# DistBoard.net
KiCad netlist of a schematic drawn in Altium Designer
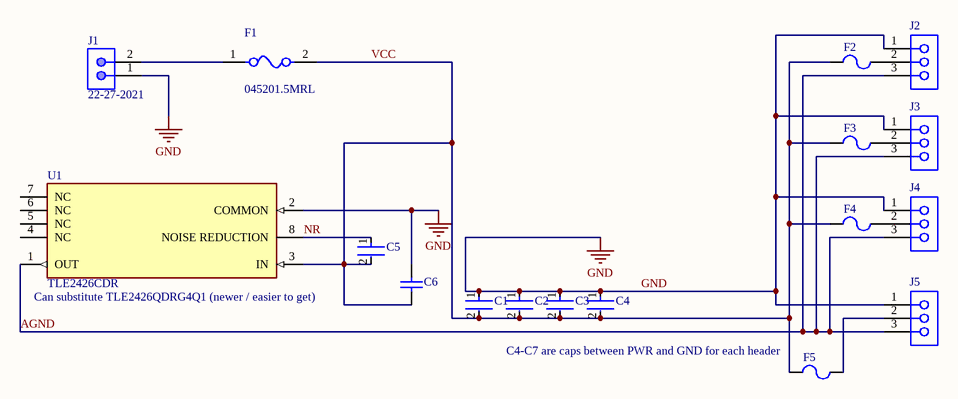
[diagram p0: DistBoard.SchDoc]

(export (version "E")
  (design (tool "Eeschema 10.0.6"))
  (components
    (comp (ref "C1")
      (value "GCJ21BR71H105KA01L")
      (footprint "FP-GCJ21B-0_3-IPC_B")
      (fields (field (name "TOLERANCE") "10%") (field (name "MANUFACTURER") "Murata"))
      (libsource (lib "Altium Content Vault") (part "02cd4be3c70576c341d710602a673aa"))
    )
    (comp (ref "C2")
      (value "GCJ21BR71H105KA01L")
      (footprint "FP-GCJ21B-0_3-IPC_B")
      (fields (field (name "TOLERANCE") "10%") (field (name "MANUFACTURER") "Murata"))
      (libsource (lib "Altium Content Vault") (part "02cd4be3c70576c341d710602a673aa"))
    )
    (comp (ref "C3")
      (value "GCJ21BR71H105KA01L")
      (footprint "FP-GCJ21B-0_3-IPC_B")
      (fields (field (name "TOLERANCE") "10%") (field (name "MANUFACTURER") "Murata"))
      (libsource (lib "Altium Content Vault") (part "02cd4be3c70576c341d710602a673aa"))
    )
    (comp (ref "C4")
      (value "GCJ21BR71H105KA01L")
      (footprint "FP-GCJ21B-0_3-IPC_B")
      (fields (field (name "TOLERANCE") "10%") (field (name "MANUFACTURER") "Murata"))
      (libsource (lib "Altium Content Vault") (part "02cd4be3c70576c341d710602a673aa"))
    )
    (comp (ref "C5")
      (value "GCD21BR71H104KA01L")
      (footprint "FP-GCD21B-0_15-IPC_C")
      (fields (field (name "TOLERANCE") "10%") (field (name "MANUFACTURER") "Murata"))
      (libsource (lib "Altium Content Vault") (part "b4654b650e69147ec39a6b967a45e02"))
    )
    (comp (ref "C6")
      (value "C1206C105K5RACTU")
      (footprint "CAPC3216X110X50LL20T25")
      (description "Chip Capacitor, 1 uF, +/- 10%, 50 V, -55 to 125 degC, 1206 (3216 Metric), RoHS, Tape and Reel")
      (fields (field (name "MANUFACTURER") "Kemet") (field (name "TOLERANCE") "10%"))
      (libsource (lib "Altium Content Vault") (part "CAP-NP-2"))
    )
    (comp (ref "F1")
      (value "045201.5MRL")
      (footprint "FP-0452-MFG")
      (description "FUSE BRD MNT 1.5A 125VAC/VDC SMD")
      (fields
        (field (name "MANUFACTURER") "Littelfuse Inc")
        (field (name "OCTOPART") "https://octopart.com/045201.5mrl-littelfuse-566412")
      )
      (libsource (lib "Altium Content Vault") (part "5bcf9b9f640e542cf0359d10258e979"))
    )
    (comp (ref "F2")
      (value "0459.250UR")
      (footprint "LFUS-459_V")
      (description "Fuse, 125 V, 250 mA, -55 to 125 degC, 2-Pin SMD, RoHS, Tape and Reel")
      (fields (field (name "MANUFACTURER") "Littelfuse"))
      (libsource (lib "Altium Content Vault") (part "FUSE-2"))
    )
    (comp (ref "F3")
      (value "0459.250UR")
      (footprint "LFUS-459_V")
      (description "Fuse, 125 V, 250 mA, -55 to 125 degC, 2-Pin SMD, RoHS, Tape and Reel")
      (fields (field (name "MANUFACTURER") "Littelfuse"))
      (libsource (lib "Altium Content Vault") (part "FUSE-2"))
    )
    (comp (ref "F4")
      (value "0459.250UR")
      (footprint "LFUS-459_V")
      (description "Fuse, 125 V, 250 mA, -55 to 125 degC, 2-Pin SMD, RoHS, Tape and Reel")
      (fields (field (name "MANUFACTURER") "Littelfuse"))
      (libsource (lib "Altium Content Vault") (part "FUSE-2"))
    )
    (comp (ref "F5")
      (value "0459.250UR")
      (footprint "LFUS-459_V")
      (description "Fuse, 125 V, 250 mA, -55 to 125 degC, 2-Pin SMD, RoHS, Tape and Reel")
      (fields (field (name "MANUFACTURER") "Littelfuse"))
      (libsource (lib "Altium Content Vault") (part "FUSE-2"))
    )
    (comp (ref "J1")
      (value "22-27-2021")
      (footprint "MOLX-22-27-2021_V")
      (fields (field (name "MANUFACTURER") "Molex") (field (name "PARTNUMBER") "0022272021"))
      (libsource (lib "Altium Content Vault") (part "CN-1P-M-R2"))
    )
    (comp (ref "J2")
      (value "SSM-103-L-SV")
      (footprint "SMTC-SSM-103-X-SV")
      (fields (field (name "MANUFACTURER") "Samtec"))
      (libsource (lib "Altium Content Vault") (part "SMTC-SSM-103-X-SV"))
    )
    (comp (ref "J3")
      (value "SSM-103-L-SV")
      (footprint "SMTC-SSM-103-X-SV")
      (fields (field (name "MANUFACTURER") "Samtec"))
      (libsource (lib "Altium Content Vault") (part "SMTC-SSM-103-X-SV"))
    )
    (comp (ref "J4")
      (value "SSM-103-L-SV")
      (footprint "SMTC-SSM-103-X-SV")
      (fields (field (name "MANUFACTURER") "Samtec"))
      (libsource (lib "Altium Content Vault") (part "SMTC-SSM-103-X-SV"))
    )
    (comp (ref "J5")
      (value "SSM-103-L-SV")
      (footprint "SMTC-SSM-103-X-SV")
      (fields (field (name "MANUFACTURER") "Samtec"))
      (libsource (lib "Altium Content Vault") (part "SMTC-SSM-103-X-SV"))
    )
    (comp (ref "U1")
      (value "TLE2426CDR")
      (footprint "FP-D0008A-IPC_B")
      (fields (field (name "TOLERANCE") "1%") (field (name "MANUFACTURER") "Texas Instruments"))
      (libsource (lib "Altium Content Vault") (part "6a05ed44ac4318f8a6b310f721958da"))
    )
  )
  (nets
    (net (code "1") (name "/AGND") (class "Default")
      (node (ref "J2") (pin "3") (pinfunction "3_3") (pintype "passive"))
      (node (ref "J3") (pin "3") (pinfunction "3_3") (pintype "passive"))
      (node (ref "J4") (pin "3") (pinfunction "3_3") (pintype "passive"))
      (node (ref "J5") (pin "3") (pinfunction "3_3") (pintype "passive"))
      (node (ref "U1") (pin "1") (pinfunction "OUT_1") (pintype "output"))
    )
    (net (code "2") (name "/NR") (class "Default")
      (node (ref "C5") (pin "1") (pinfunction "1_1") (pintype "passive"))
      (node (ref "U1") (pin "8") (pinfunction "NOISE_REDUCTION_8") (pintype "passive"))
    )
    (net (code "3") (name "/VCC") (class "Default")
      (node (ref "C1") (pin "2") (pinfunction "2_2") (pintype "passive"))
      (node (ref "C2") (pin "2") (pinfunction "2_2") (pintype "passive"))
      (node (ref "C3") (pin "2") (pinfunction "2_2") (pintype "passive"))
      (node (ref "C4") (pin "2") (pinfunction "2_2") (pintype "passive"))
      (node (ref "C5") (pin "2") (pinfunction "2_2") (pintype "passive"))
      (node (ref "C6") (pin "1") (pinfunction "1_1") (pintype "passive"))
      (node (ref "F1") (pin "2") (pinfunction "2_2") (pintype "passive"))
      (node (ref "F2") (pin "1") (pinfunction "1_1") (pintype "passive"))
      (node (ref "F3") (pin "1") (pinfunction "1_1") (pintype "passive"))
      (node (ref "F4") (pin "1") (pinfunction "1_1") (pintype "passive"))
      (node (ref "F5") (pin "1") (pinfunction "1_1") (pintype "passive"))
      (node (ref "U1") (pin "3") (pinfunction "IN_3") (pintype "input"))
    )
    (net (code "4") (name "GND") (class "Default")
      (node (ref "C1") (pin "1") (pinfunction "1_1") (pintype "passive"))
      (node (ref "C2") (pin "1") (pinfunction "1_1") (pintype "passive"))
      (node (ref "C3") (pin "1") (pinfunction "1_1") (pintype "passive"))
      (node (ref "C4") (pin "1") (pinfunction "1_1") (pintype "passive"))
      (node (ref "C6") (pin "2") (pinfunction "2_2") (pintype "passive"))
      (node (ref "J1") (pin "1") (pinfunction "1_1") (pintype "passive"))
      (node (ref "J2") (pin "1") (pinfunction "1_1") (pintype "passive"))
      (node (ref "J3") (pin "1") (pinfunction "1_1") (pintype "passive"))
      (node (ref "J4") (pin "1") (pinfunction "1_1") (pintype "passive"))
      (node (ref "J5") (pin "1") (pinfunction "1_1") (pintype "passive"))
      (node (ref "U1") (pin "2") (pinfunction "COMMON_2") (pintype "input"))
    )
    (net (code "5") (name "Net-(F1-Pad1)") (class "Default")
      (node (ref "F1") (pin "1") (pinfunction "1_1") (pintype "passive"))
      (node (ref "J1") (pin "2") (pinfunction "2_2") (pintype "passive"))
    )
    (net (code "6") (name "Net-(F2-Pad2)") (class "Default")
      (node (ref "F2") (pin "2") (pinfunction "2_2") (pintype "passive"))
      (node (ref "J2") (pin "2") (pinfunction "2_2") (pintype "passive"))
    )
    (net (code "7") (name "Net-(F3-Pad2)") (class "Default")
      (node (ref "F3") (pin "2") (pinfunction "2_2") (pintype "passive"))
      (node (ref "J3") (pin "2") (pinfunction "2_2") (pintype "passive"))
    )
    (net (code "8") (name "Net-(F4-Pad2)") (class "Default")
      (node (ref "F4") (pin "2") (pinfunction "2_2") (pintype "passive"))
      (node (ref "J4") (pin "2") (pinfunction "2_2") (pintype "passive"))
    )
    (net (code "9") (name "Net-(F5-Pad2)") (class "Default")
      (node (ref "F5") (pin "2") (pinfunction "2_2") (pintype "passive"))
      (node (ref "J5") (pin "2") (pinfunction "2_2") (pintype "passive"))
    )
    (net (code "10") (name "unconnected-(U1-NC-Pad4)") (class "Default")
      (node (ref "U1") (pin "4") (pinfunction "NC_4") (pintype "passive"))
    )
    (net (code "11") (name "unconnected-(U1-NC-Pad5)") (class "Default")
      (node (ref "U1") (pin "5") (pinfunction "NC_5") (pintype "passive"))
    )
    (net (code "12") (name "unconnected-(U1-NC-Pad6)") (class "Default")
      (node (ref "U1") (pin "6") (pinfunction "NC_6") (pintype "passive"))
    )
    (net (code "13") (name "unconnected-(U1-NC-Pad7)") (class "Default")
      (node (ref "U1") (pin "7") (pinfunction "NC_7") (pintype "passive"))
    )
  )
)
